# 2s-module.net
KiCad netlist of a schematic drawn in EAGLE
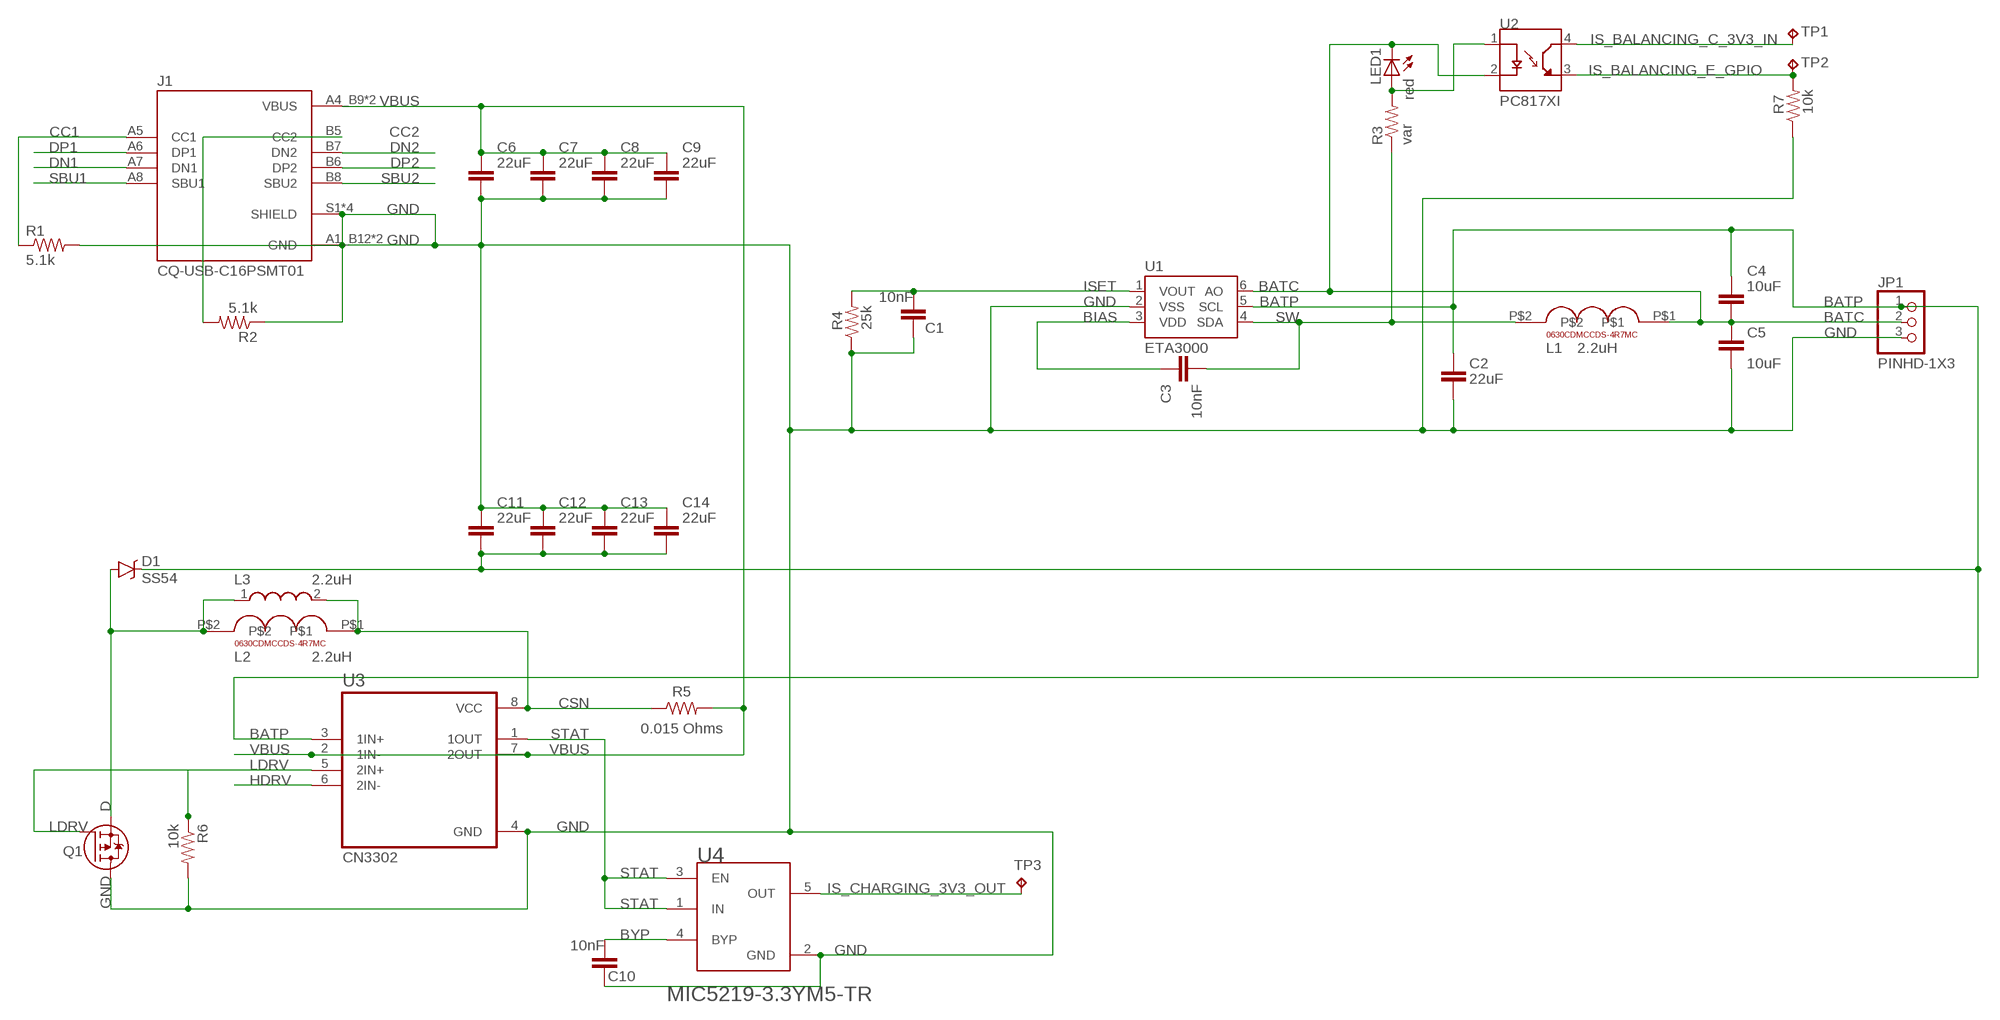
[diagram p0: schematic, sheet 1]

(export (version "E")
  (design (tool "Eeschema 10.0.6"))
  (components
    (comp (ref "C1")
      (value "10nF")
      (footprint "eagle-import:CAPC1608X85")
      (libsource (lib "eagle-import") (part "CCHIP-0603(1608-METRIC)_"))
    )
    (comp (ref "C2")
      (value "22uF")
      (footprint "eagle-import:CAPC3216X135")
      (libsource (lib "eagle-import") (part "CCHIP-1206(3216-METRIC)_"))
    )
    (comp (ref "C3")
      (value "10nF")
      (footprint "eagle-import:CAPC1608X85")
      (libsource (lib "eagle-import") (part "CCHIP-0603(1608-METRIC)_"))
    )
    (comp (ref "C4")
      (value "10uF")
      (footprint "eagle-import:CAPC1608X85")
      (libsource (lib "eagle-import") (part "CCHIP-0603(1608-METRIC)_"))
    )
    (comp (ref "C5")
      (value "10uF")
      (footprint "eagle-import:CAPC1608X85")
      (libsource (lib "eagle-import") (part "CCHIP-0603(1608-METRIC)_"))
    )
    (comp (ref "C6")
      (value "22uF")
      (footprint "eagle-import:CAPC3216X135")
      (libsource (lib "eagle-import") (part "CCHIP-1206(3216-METRIC)_"))
    )
    (comp (ref "C7")
      (value "22uF")
      (footprint "eagle-import:CAPC3216X135")
      (libsource (lib "eagle-import") (part "CCHIP-1206(3216-METRIC)_"))
    )
    (comp (ref "C8")
      (value "22uF")
      (footprint "eagle-import:CAPC3216X135")
      (libsource (lib "eagle-import") (part "CCHIP-1206(3216-METRIC)_"))
    )
    (comp (ref "C9")
      (value "22uF")
      (footprint "eagle-import:CAPC3216X135")
      (libsource (lib "eagle-import") (part "CCHIP-1206(3216-METRIC)_"))
    )
    (comp (ref "C10")
      (value "10nF")
      (footprint "eagle-import:CAPC1608X85")
      (libsource (lib "eagle-import") (part "CCHIP-0603(1608-METRIC)_"))
    )
    (comp (ref "C11")
      (value "22uF")
      (footprint "eagle-import:CAPC3216X135")
      (libsource (lib "eagle-import") (part "CCHIP-1206(3216-METRIC)_"))
    )
    (comp (ref "C12")
      (value "22uF")
      (footprint "eagle-import:CAPC3216X135")
      (libsource (lib "eagle-import") (part "CCHIP-1206(3216-METRIC)_"))
    )
    (comp (ref "C13")
      (value "22uF")
      (footprint "eagle-import:CAPC3216X135")
      (libsource (lib "eagle-import") (part "CCHIP-1206(3216-METRIC)_"))
    )
    (comp (ref "C14")
      (value "22uF")
      (footprint "eagle-import:CAPC3216X135")
      (libsource (lib "eagle-import") (part "CCHIP-1206(3216-METRIC)_"))
    )
    (comp (ref "D1")
      (value "SS54")
      (footprint "eagle-import:DO-214AC")
      (fields (field (name "MF") "MDD"))
      (libsource (lib "eagle-import") (part "SS54"))
    )
    (comp (ref "J1")
      (value "CQ-USB-C16PSMT01")
      (footprint "eagle-import:SHENZHEN-CHUANGQIN-TECHNOLOGY_CQ-USB-C16PSMT01")
      (fields (field (name "MF") "Shenzen Chuangqin Technology"))
      (libsource (lib "eagle-import") (part "CQ-USB-C16PSMT01"))
    )
    (comp (ref "JP1")
      (value "PINHD-1X3")
      (footprint "eagle-import:1X03")
      (fields (field (name "MANUFACTURER") "Generic"))
      (libsource (lib "eagle-import") (part "PINHD-1X3"))
    )
    (comp (ref "L1")
      (value "0630CDMCCDS-4R7MC")
      (footprint "eagle-import:0630CDMCCDS-4R7MC")
      (fields (field (name "MF") "Sumida"))
      (libsource (lib "eagle-import") (part "0630CDMCCDS-4R7MC"))
    )
    (comp (ref "L2")
      (value "2.2uH")
      (footprint "eagle-import:0630CDMCCDS-4R7MC")
      (fields (field (name "MF") "Sumida") (field (name "MP") "0630CDMCCDS-4R7MC"))
      (libsource (lib "eagle-import") (part "0630CDMCCDS-4R7MC"))
    )
    (comp (ref "L3")
      (value "2.2uH")
      (footprint "eagle-import:INDM110100X380N")
      (fields (field (name "MF") "Wurth Electronics") (field (name "MP") "74437368047"))
      (libsource (lib "eagle-import") (part "74437368047"))
    )
    (comp (ref "LED1")
      (value "red")
      (footprint "eagle-import:CHIPLED_0603")
      (libsource (lib "eagle-import") (part "LEDCHIPLED_0603"))
    )
    (comp (ref "Q1")
      (value "IRFR9020A")
      (footprint "eagle-import:TO252")
      (libsource (lib "eagle-import") (part "IRFR9020A"))
    )
    (comp (ref "R1")
      (value "5.1k")
      (footprint "eagle-import:R0603")
      (libsource (lib "eagle-import") (part "R-US_R0603"))
    )
    (comp (ref "R2")
      (value "5.1k")
      (footprint "eagle-import:R0603")
      (libsource (lib "eagle-import") (part "R-US_R0603"))
    )
    (comp (ref "R3")
      (value "var")
      (footprint "eagle-import:R0603")
      (libsource (lib "eagle-import") (part "R-US_R0603"))
    )
    (comp (ref "R4")
      (value "25k")
      (footprint "eagle-import:R0603")
      (libsource (lib "eagle-import") (part "R-US_R0603"))
    )
    (comp (ref "R5")
      (value "0.015 Ohms")
      (footprint "eagle-import:RESC6332X71")
      (libsource (lib "eagle-import") (part "R-USCHIP-2512(6332-METRIC)_"))
    )
    (comp (ref "R6")
      (value "10k")
      (footprint "eagle-import:R0603")
      (libsource (lib "eagle-import") (part "R-US_R0603"))
    )
    (comp (ref "R7")
      (value "10k")
      (footprint "eagle-import:R0603")
      (libsource (lib "eagle-import") (part "R-US_R0603"))
    )
    (comp (ref "TP1")
      (value "TPB1,27")
      (footprint "eagle-import:B1,27")
      (libsource (lib "eagle-import") (part "TPB1,27"))
    )
    (comp (ref "TP2")
      (value "TPB1,27")
      (footprint "eagle-import:B1,27")
      (libsource (lib "eagle-import") (part "TPB1,27"))
    )
    (comp (ref "TP3")
      (value "TPB1,27")
      (footprint "eagle-import:B1,27")
      (libsource (lib "eagle-import") (part "TPB1,27"))
    )
    (comp (ref "U1")
      (value "MCP4725")
      (footprint "eagle-import:SOT23-6")
      (libsource (lib "eagle-import") (part "MCP4725SOT-23"))
    )
    (comp (ref "U2")
      (value "PC817XI")
      (footprint "eagle-import:SOIC254P975X460-4N")
      (fields (field (name "MF") "Sharp Microelectronics"))
      (libsource (lib "eagle-import") (part "PC817XI"))
    )
    (comp (ref "U3")
      (value "LM393DR")
      (footprint "eagle-import:SOIC127P599X175-8N")
      (fields (field (name "MF") "Texas Instruments"))
      (libsource (lib "eagle-import") (part "LM393DR"))
    )
    (comp (ref "U4")
      (value "MICROCHIP_MIC5219-3_3YM5-TRMICROCHIP_MIC5219-3_3YM5-TR_0_0")
      (footprint "eagle-import:MICROCHIP_MIC5219-3_3YM5-TR_0")
      (fields
        (field (name "DIGIKEY_PART_NUMBER") "576-1281-1-ND")
        (field (name "MF") "Microchip")
        (field (name "MOUSER_PART_NUMBER") "998-MIC5219-3.3YM5TR")
      )
      (libsource (lib "eagle-import") (part "MICROCHIP_MIC5219-3_3YM5-TRMICROCHIP_MIC5219-3_3YM5-TR_0_0"))
    )
  )
  (nets
    (net (code "1") (name "/BATC") (class "Default")
      (node (ref "C4") (pin "2") (pinfunction "2_2") (pintype "passive"))
      (node (ref "C5") (pin "1") (pinfunction "1_1") (pintype "passive"))
      (node (ref "JP1") (pin "2") (pinfunction "2_2") (pintype "passive"))
      (node (ref "L1") (pin "P$1") (pinfunction "P$1_P$1") (pintype "bidirectional"))
      (node (ref "LED1") (pin "C") (pinfunction "C_C") (pintype "passive"))
      (node (ref "U1") (pin "6") (pinfunction "AO_6") (pintype "bidirectional"))
      (node (ref "U2") (pin "2") (pinfunction "C_2") (pintype "passive"))
    )
    (net (code "2") (name "/BATP") (class "Default")
      (node (ref "C11") (pin "2") (pinfunction "2_2") (pintype "passive"))
      (node (ref "C12") (pin "2") (pinfunction "2_2") (pintype "passive"))
      (node (ref "C13") (pin "2") (pinfunction "2_2") (pintype "passive"))
      (node (ref "C14") (pin "2") (pinfunction "2_2") (pintype "passive"))
      (node (ref "C2") (pin "1") (pinfunction "1_1") (pintype "passive"))
      (node (ref "C4") (pin "1") (pinfunction "1_1") (pintype "passive"))
      (node (ref "D1") (pin "C") (pinfunction "C_C") (pintype "passive"))
      (node (ref "JP1") (pin "1") (pinfunction "1_1") (pintype "passive"))
      (node (ref "U1") (pin "5") (pinfunction "SCL_5") (pintype "bidirectional"))
      (node (ref "U3") (pin "3") (pinfunction "1IN+_3") (pintype "input"))
    )
    (net (code "3") (name "/BIAS") (class "Default")
      (node (ref "C3") (pin "2") (pinfunction "2_2") (pintype "passive"))
      (node (ref "U1") (pin "3") (pinfunction "VDD_3") (pintype "bidirectional"))
    )
    (net (code "4") (name "/BYP") (class "Default")
      (node (ref "C10") (pin "2") (pinfunction "2_2") (pintype "passive"))
      (node (ref "U4") (pin "4") (pinfunction "BYP_4") (pintype "passive"))
    )
    (net (code "5") (name "/CC1") (class "Default")
      (node (ref "J1") (pin "A5") (pinfunction "CC1_A5") (pintype "bidirectional"))
      (node (ref "R1") (pin "1") (pinfunction "1_1") (pintype "passive"))
    )
    (net (code "6") (name "/CC2") (class "Default")
      (node (ref "J1") (pin "B5") (pinfunction "CC2_B5") (pintype "bidirectional"))
      (node (ref "R2") (pin "2") (pinfunction "2_2") (pintype "passive"))
    )
    (net (code "7") (name "/CSN") (class "Default")
      (node (ref "L2") (pin "P$1") (pinfunction "P$1_P$1") (pintype "bidirectional"))
      (node (ref "L3") (pin "2") (pinfunction "2_2") (pintype "passive"))
      (node (ref "R5") (pin "1") (pinfunction "1_1") (pintype "passive"))
      (node (ref "U3") (pin "8") (pinfunction "VCC_8") (pintype "power_in"))
    )
    (net (code "8") (name "/D") (class "Default")
      (node (ref "D1") (pin "A") (pinfunction "A_A") (pintype "passive"))
      (node (ref "L2") (pin "P$2") (pinfunction "P$2_P$2") (pintype "bidirectional"))
      (node (ref "L3") (pin "1") (pinfunction "1_1") (pintype "passive"))
      (node (ref "Q1") (pin "2") (pinfunction "S_2") (pintype "passive"))
    )
    (net (code "9") (name "/DN1") (class "Default")
      (node (ref "J1") (pin "A7") (pinfunction "DN1_A7") (pintype "bidirectional"))
    )
    (net (code "10") (name "/DN2") (class "Default")
      (node (ref "J1") (pin "B7") (pinfunction "DN2_B7") (pintype "bidirectional"))
    )
    (net (code "11") (name "/DP1") (class "Default")
      (node (ref "J1") (pin "A6") (pinfunction "DP1_A6") (pintype "bidirectional"))
    )
    (net (code "12") (name "/DP2") (class "Default")
      (node (ref "J1") (pin "B6") (pinfunction "DP2_B6") (pintype "bidirectional"))
    )
    (net (code "13") (name "/GND") (class "Default")
      (node (ref "C1") (pin "1") (pinfunction "1_1") (pintype "passive"))
      (node (ref "C10") (pin "1") (pinfunction "1_1") (pintype "passive"))
      (node (ref "C11") (pin "1") (pinfunction "1_1") (pintype "passive"))
      (node (ref "C12") (pin "1") (pinfunction "1_1") (pintype "passive"))
      (node (ref "C13") (pin "1") (pinfunction "1_1") (pintype "passive"))
      (node (ref "C14") (pin "1") (pinfunction "1_1") (pintype "passive"))
      (node (ref "C2") (pin "2") (pinfunction "2_2") (pintype "passive"))
      (node (ref "C5") (pin "2") (pinfunction "2_2") (pintype "passive"))
      (node (ref "C6") (pin "2") (pinfunction "2_2") (pintype "passive"))
      (node (ref "C7") (pin "2") (pinfunction "2_2") (pintype "passive"))
      (node (ref "C8") (pin "2") (pinfunction "2_2") (pintype "passive"))
      (node (ref "C9") (pin "2") (pinfunction "2_2") (pintype "passive"))
      (node (ref "J1") (pin "A1_B12") (pinfunction "GND_A1_B12") (pintype "power_in"))
      (node (ref "J1") (pin "B1_A12") (pinfunction "GND_B1_A12") (pintype "power_in"))
      (node (ref "J1") (pin "S1") (pinfunction "SHIELD_S1") (pintype "passive"))
      (node (ref "J1") (pin "S2") (pinfunction "SHIELD_S2") (pintype "passive"))
      (node (ref "J1") (pin "S3") (pinfunction "SHIELD_S3") (pintype "passive"))
      (node (ref "J1") (pin "S4") (pinfunction "SHIELD_S4") (pintype "passive"))
      (node (ref "JP1") (pin "3") (pinfunction "3_3") (pintype "passive"))
      (node (ref "Q1") (pin "3") (pinfunction "D_3") (pintype "passive"))
      (node (ref "R1") (pin "2") (pinfunction "2_2") (pintype "passive"))
      (node (ref "R2") (pin "1") (pinfunction "1_1") (pintype "passive"))
      (node (ref "R4") (pin "1") (pinfunction "1_1") (pintype "passive"))
      (node (ref "R6") (pin "2") (pinfunction "2_2") (pintype "passive"))
      (node (ref "R7") (pin "1") (pinfunction "1_1") (pintype "passive"))
      (node (ref "U1") (pin "2") (pinfunction "VSS_2") (pintype "bidirectional"))
      (node (ref "U3") (pin "4") (pinfunction "GND_4") (pintype "power_in"))
      (node (ref "U4") (pin "2") (pinfunction "GND_2") (pintype "power_in"))
    )
    (net (code "14") (name "/HDRV") (class "Default")
      (node (ref "U3") (pin "6") (pinfunction "2IN-_6") (pintype "input"))
    )
    (net (code "15") (name "/ISET") (class "Default")
      (node (ref "C1") (pin "2") (pinfunction "2_2") (pintype "passive"))
      (node (ref "R4") (pin "2") (pinfunction "2_2") (pintype "passive"))
      (node (ref "U1") (pin "1") (pinfunction "VOUT_1") (pintype "bidirectional"))
    )
    (net (code "16") (name "/IS_BALANCING_C_3V3_IN") (class "Default")
      (node (ref "TP1") (pin "TP") (pinfunction "TP_TP") (pintype "input"))
      (node (ref "U2") (pin "4") (pinfunction "CT_4") (pintype "passive"))
    )
    (net (code "17") (name "/IS_BALANCING_E_GPIO") (class "Default")
      (node (ref "R7") (pin "2") (pinfunction "2_2") (pintype "passive"))
      (node (ref "TP2") (pin "TP") (pinfunction "TP_TP") (pintype "input"))
      (node (ref "U2") (pin "3") (pinfunction "ET_3") (pintype "passive"))
    )
    (net (code "18") (name "/IS_CHARGING_3V3_OUT") (class "Default")
      (node (ref "TP3") (pin "TP") (pinfunction "TP_TP") (pintype "input"))
      (node (ref "U4") (pin "5") (pinfunction "OUT_5") (pintype "output"))
    )
    (net (code "19") (name "/LDRV") (class "Default")
      (node (ref "Q1") (pin "1") (pinfunction "G_1") (pintype "passive"))
      (node (ref "R6") (pin "1") (pinfunction "1_1") (pintype "passive"))
      (node (ref "U3") (pin "5") (pinfunction "2IN+_5") (pintype "input"))
    )
    (net (code "20") (name "/SBU1") (class "Default")
      (node (ref "J1") (pin "A8") (pinfunction "SBU1_A8") (pintype "bidirectional"))
    )
    (net (code "21") (name "/SBU2") (class "Default")
      (node (ref "J1") (pin "B8") (pinfunction "SBU2_B8") (pintype "bidirectional"))
    )
    (net (code "22") (name "/STAT") (class "Default")
      (node (ref "U3") (pin "1") (pinfunction "1OUT_1") (pintype "output"))
      (node (ref "U4") (pin "1") (pinfunction "IN_1") (pintype "input"))
      (node (ref "U4") (pin "3") (pinfunction "EN_3") (pintype "input"))
    )
    (net (code "23") (name "/SW") (class "Default")
      (node (ref "C3") (pin "1") (pinfunction "1_1") (pintype "passive"))
      (node (ref "L1") (pin "P$2") (pinfunction "P$2_P$2") (pintype "bidirectional"))
      (node (ref "R3") (pin "1") (pinfunction "1_1") (pintype "passive"))
      (node (ref "U1") (pin "4") (pinfunction "SDA_4") (pintype "bidirectional"))
    )
    (net (code "24") (name "/VBUS") (class "Default")
      (node (ref "C6") (pin "1") (pinfunction "1_1") (pintype "passive"))
      (node (ref "C7") (pin "1") (pinfunction "1_1") (pintype "passive"))
      (node (ref "C8") (pin "1") (pinfunction "1_1") (pintype "passive"))
      (node (ref "C9") (pin "1") (pinfunction "1_1") (pintype "passive"))
      (node (ref "J1") (pin "A4_B9") (pinfunction "VBUS_A4_B9") (pintype "power_in"))
      (node (ref "J1") (pin "B4_A9") (pinfunction "VBUS_B4_A9") (pintype "power_in"))
      (node (ref "R5") (pin "2") (pinfunction "2_2") (pintype "passive"))
      (node (ref "U3") (pin "2") (pinfunction "1IN-_2") (pintype "input"))
      (node (ref "U3") (pin "7") (pinfunction "2OUT_7") (pintype "output"))
    )
    (net (code "25") (name "Net-(U2-A)") (class "Default")
      (node (ref "LED1") (pin "A") (pinfunction "A_A") (pintype "passive"))
      (node (ref "R3") (pin "2") (pinfunction "2_2") (pintype "passive"))
      (node (ref "U2") (pin "1") (pinfunction "A_1") (pintype "passive"))
    )
  )
)
